# nRF24L01.net
KiCad netlist of a schematic drawn in Altium Designer
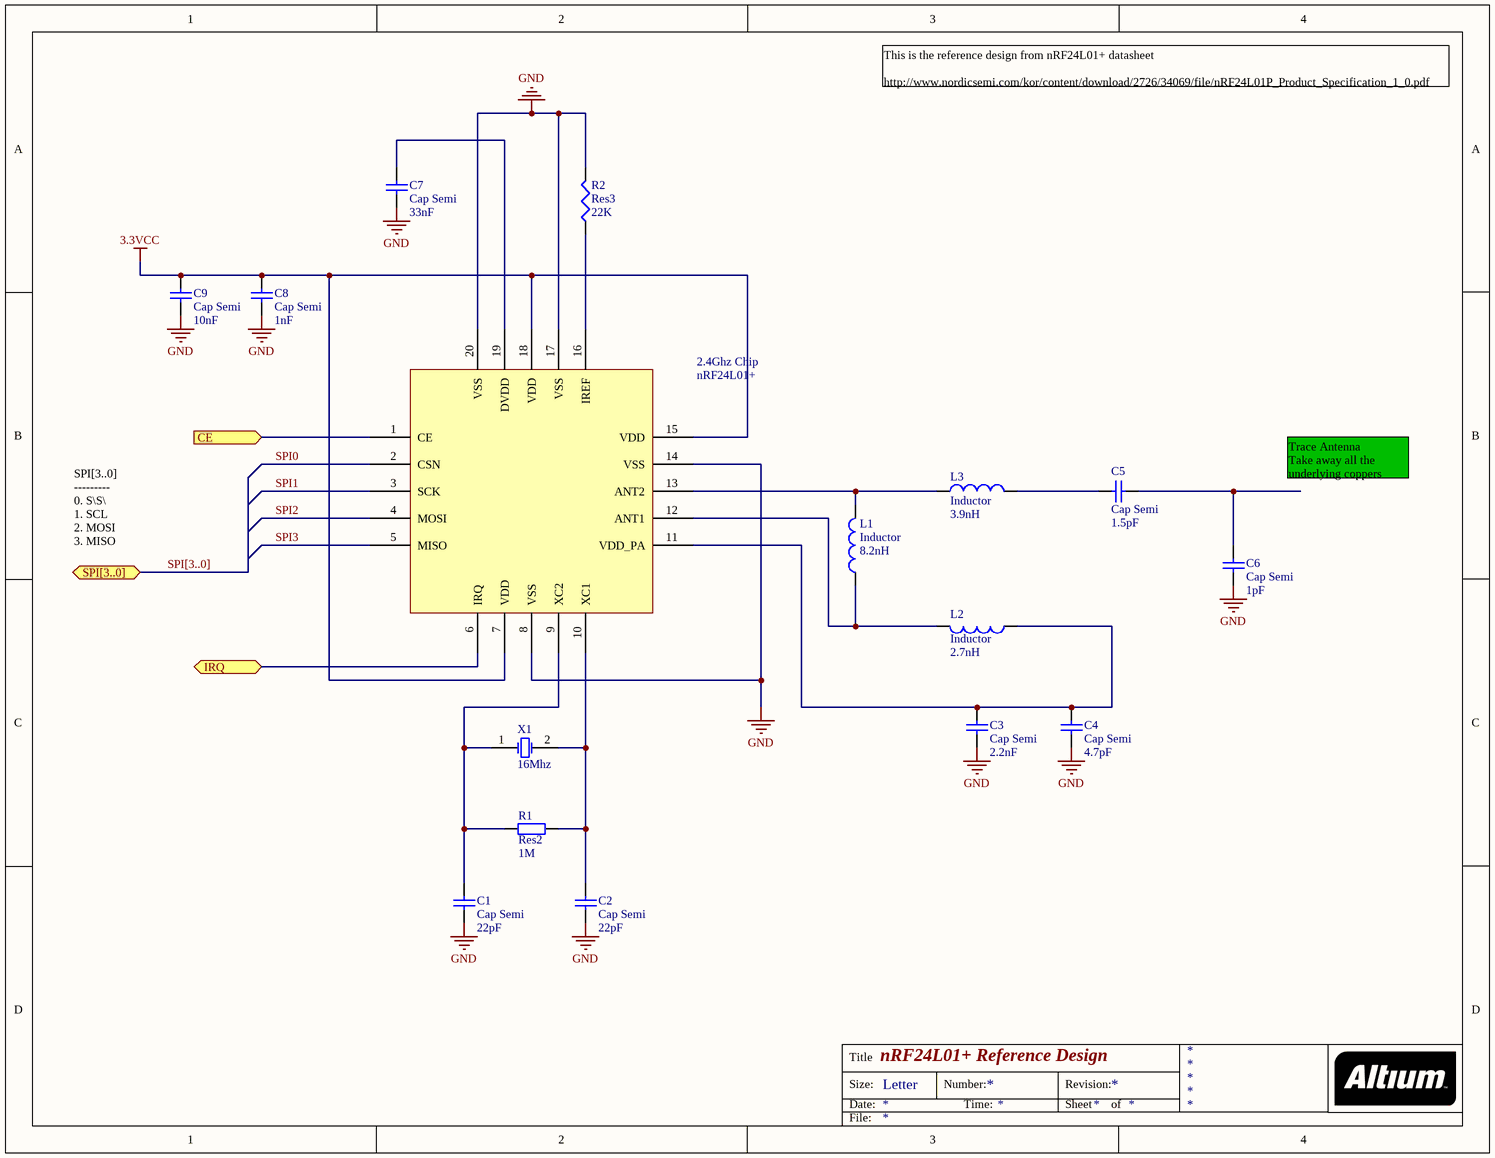
[diagram p0: nRF24L01+.SchDoc]

(export (version "E")
  (design (tool "Eeschema 10.0.6"))
  (components
    (comp (ref "2.4Ghz Chip")
      (value "nRF24L01+")
      (footprint "nRF24L01+")
      (libsource (lib "nRF24L01+") (part "nRF24L01+"))
    )
    (comp (ref "C1")
      (value "Cap Semi")
      (footprint "CAPC2012N")
      (description "Capacitor (Semiconductor SIM Model)")
      (fields (field (name "ALTIUM_VALUE") "22pF") (field (name "PUBLISHER") "Altium Limited"))
      (libsource (lib "Miscellaneous Devices") (part "Cap Semi"))
    )
    (comp (ref "C2")
      (value "Cap Semi")
      (footprint "CAPC2012N")
      (description "Capacitor (Semiconductor SIM Model)")
      (fields (field (name "ALTIUM_VALUE") "22pF") (field (name "PUBLISHER") "Altium Limited"))
      (libsource (lib "Miscellaneous Devices") (part "Cap Semi"))
    )
    (comp (ref "C3")
      (value "Cap Semi")
      (footprint "CAPC2012N")
      (description "Capacitor (Semiconductor SIM Model)")
      (fields (field (name "ALTIUM_VALUE") "2.2nF") (field (name "PUBLISHER") "Altium Limited"))
      (libsource (lib "Miscellaneous Devices") (part "Cap Semi"))
    )
    (comp (ref "C4")
      (value "Cap Semi")
      (footprint "CAPC2012N")
      (description "Capacitor (Semiconductor SIM Model)")
      (fields (field (name "ALTIUM_VALUE") "4.7pF") (field (name "PUBLISHER") "Altium Limited"))
      (libsource (lib "Miscellaneous Devices") (part "Cap Semi"))
    )
    (comp (ref "C5")
      (value "Cap Semi")
      (footprint "CAPC2012N")
      (description "Capacitor (Semiconductor SIM Model)")
      (fields (field (name "ALTIUM_VALUE") "1.5pF") (field (name "PUBLISHER") "Altium Limited"))
      (libsource (lib "Miscellaneous Devices") (part "Cap Semi"))
    )
    (comp (ref "C6")
      (value "Cap Semi")
      (footprint "CAPC2012N")
      (description "Capacitor (Semiconductor SIM Model)")
      (fields (field (name "ALTIUM_VALUE") "1pF") (field (name "PUBLISHER") "Altium Limited"))
      (libsource (lib "Miscellaneous Devices") (part "Cap Semi"))
    )
    (comp (ref "C7")
      (value "Cap Semi")
      (footprint "CAPC2012N")
      (description "Capacitor (Semiconductor SIM Model)")
      (fields (field (name "ALTIUM_VALUE") "33nF") (field (name "PUBLISHER") "Altium Limited"))
      (libsource (lib "Miscellaneous Devices") (part "Cap Semi"))
    )
    (comp (ref "C8")
      (value "Cap Semi")
      (footprint "CAPC2012N")
      (description "Capacitor (Semiconductor SIM Model)")
      (fields (field (name "ALTIUM_VALUE") "1nF") (field (name "PUBLISHER") "Altium Limited"))
      (libsource (lib "Miscellaneous Devices") (part "Cap Semi"))
    )
    (comp (ref "C9")
      (value "Cap Semi")
      (footprint "CAPC2012N")
      (description "Capacitor (Semiconductor SIM Model)")
      (fields (field (name "ALTIUM_VALUE") "10nF") (field (name "PUBLISHER") "Altium Limited"))
      (libsource (lib "Miscellaneous Devices") (part "Cap Semi"))
    )
    (comp (ref "L1")
      (value "Inductor")
      (footprint "INDC1608N")
      (fields (field (name "ALTIUM_VALUE") "8.2nH") (field (name "PUBLISHER") "Altium Limited"))
      (libsource (lib "Miscellaneous Devices") (part "Inductor"))
    )
    (comp (ref "L2")
      (value "Inductor")
      (footprint "INDC1608N")
      (fields (field (name "ALTIUM_VALUE") "2.7nH") (field (name "PUBLISHER") "Altium Limited"))
      (libsource (lib "Miscellaneous Devices") (part "Inductor"))
    )
    (comp (ref "L3")
      (value "Inductor")
      (footprint "INDC1608N")
      (fields (field (name "ALTIUM_VALUE") "3.9nH") (field (name "PUBLISHER") "Altium Limited"))
      (libsource (lib "Miscellaneous Devices") (part "Inductor"))
    )
    (comp (ref "R1")
      (value "Res2")
      (footprint "RESC2012N")
      (description "Resistor")
      (fields (field (name "ALTIUM_VALUE") "1M") (field (name "PUBLISHER") "Altium Limited"))
      (libsource (lib "Miscellaneous Devices") (part "Res2"))
    )
    (comp (ref "R2")
      (value "Res3")
      (footprint "RESC2012N")
      (description "Resistor")
      (fields (field (name "ALTIUM_VALUE") "22K") (field (name "PUBLISHER") "Altium Limited"))
      (libsource (lib "Miscellaneous Devices") (part "Res3"))
    )
    (comp (ref "X1")
      (value "16Mhz")
      (footprint "HC-49U - Through Hole")
      (description "Crystal Oscillator")
      (fields (field (name "PUBLISHER") "Altium Limited"))
      (libsource (lib "Miscellaneous Devices") (part "XTAL"))
    )
  )
  (nets
    (net (code "1") (name "/CE") (class "Default")
      (node (ref "2.4Ghz Chip") (pin "1") (pinfunction "CE_1") (pintype "passive"))
    )
    (net (code "2") (name "/IRQ") (class "Default")
      (node (ref "2.4Ghz Chip") (pin "6") (pinfunction "IRQ_6") (pintype "passive"))
    )
    (net (code "3") (name "/SPI0") (class "Default")
      (node (ref "2.4Ghz Chip") (pin "2") (pinfunction "CSN_2") (pintype "passive"))
    )
    (net (code "4") (name "/SPI1") (class "Default")
      (node (ref "2.4Ghz Chip") (pin "3") (pinfunction "SCK_3") (pintype "passive"))
    )
    (net (code "5") (name "/SPI2") (class "Default")
      (node (ref "2.4Ghz Chip") (pin "4") (pinfunction "MOSI_4") (pintype "passive"))
    )
    (net (code "6") (name "/SPI3") (class "Default")
      (node (ref "2.4Ghz Chip") (pin "5") (pinfunction "MISO_5") (pintype "passive"))
    )
    (net (code "8") (name "3.3VCC") (class "Default")
      (node (ref "2.4Ghz Chip") (pin "15") (pinfunction "VDD_15") (pintype "passive"))
      (node (ref "2.4Ghz Chip") (pin "18") (pinfunction "VDD_18") (pintype "passive"))
      (node (ref "2.4Ghz Chip") (pin "7") (pinfunction "VDD_7") (pintype "passive"))
      (node (ref "C8") (pin "2") (pinfunction "2_2") (pintype "passive"))
      (node (ref "C9") (pin "2") (pinfunction "2_2") (pintype "passive"))
    )
    (net (code "9") (name "GND") (class "Default")
      (node (ref "2.4Ghz Chip") (pin "14") (pinfunction "VSS_14") (pintype "passive"))
      (node (ref "2.4Ghz Chip") (pin "17") (pinfunction "VSS_17") (pintype "passive"))
      (node (ref "2.4Ghz Chip") (pin "20") (pinfunction "VSS_20") (pintype "passive"))
      (node (ref "2.4Ghz Chip") (pin "8") (pinfunction "VSS_8") (pintype "passive"))
      (node (ref "C1") (pin "1") (pinfunction "1_1") (pintype "passive"))
      (node (ref "C2") (pin "1") (pinfunction "1_1") (pintype "passive"))
      (node (ref "C3") (pin "1") (pinfunction "1_1") (pintype "passive"))
      (node (ref "C4") (pin "1") (pinfunction "1_1") (pintype "passive"))
      (node (ref "C6") (pin "1") (pinfunction "1_1") (pintype "passive"))
      (node (ref "C7") (pin "1") (pinfunction "1_1") (pintype "passive"))
      (node (ref "C8") (pin "1") (pinfunction "1_1") (pintype "passive"))
      (node (ref "C9") (pin "1") (pinfunction "1_1") (pintype "passive"))
      (node (ref "R2") (pin "2") (pinfunction "2_2") (pintype "passive"))
    )
    (net (code "10") (name "Net-(2.4Ghz Chip-ANT1)") (class "Default")
      (node (ref "2.4Ghz Chip") (pin "12") (pinfunction "ANT1_12") (pintype "passive"))
      (node (ref "L1") (pin "1") (pinfunction "1_1") (pintype "passive"))
      (node (ref "L2") (pin "2") (pinfunction "2_2") (pintype "passive"))
    )
    (net (code "11") (name "Net-(2.4Ghz Chip-ANT2)") (class "Default")
      (node (ref "2.4Ghz Chip") (pin "13") (pinfunction "ANT2_13") (pintype "passive"))
      (node (ref "L1") (pin "2") (pinfunction "2_2") (pintype "passive"))
      (node (ref "L3") (pin "1") (pinfunction "1_1") (pintype "passive"))
    )
    (net (code "12") (name "Net-(2.4Ghz Chip-DVDD)") (class "Default")
      (node (ref "2.4Ghz Chip") (pin "19") (pinfunction "DVDD_19") (pintype "passive"))
      (node (ref "C7") (pin "2") (pinfunction "2_2") (pintype "passive"))
    )
    (net (code "13") (name "Net-(2.4Ghz Chip-IREF)") (class "Default")
      (node (ref "2.4Ghz Chip") (pin "16") (pinfunction "IREF_16") (pintype "passive"))
      (node (ref "R2") (pin "1") (pinfunction "1_1") (pintype "passive"))
    )
    (net (code "14") (name "Net-(2.4Ghz Chip-VDD_PA)") (class "Default")
      (node (ref "2.4Ghz Chip") (pin "11") (pinfunction "VDD_PA_11") (pintype "passive"))
      (node (ref "C3") (pin "2") (pinfunction "2_2") (pintype "passive"))
      (node (ref "C4") (pin "2") (pinfunction "2_2") (pintype "passive"))
      (node (ref "L2") (pin "1") (pinfunction "1_1") (pintype "passive"))
    )
    (net (code "15") (name "Net-(2.4Ghz Chip-XC1)") (class "Default")
      (node (ref "2.4Ghz Chip") (pin "10") (pinfunction "XC1_10") (pintype "passive"))
      (node (ref "C2") (pin "2") (pinfunction "2_2") (pintype "passive"))
      (node (ref "R1") (pin "2") (pinfunction "2_2") (pintype "passive"))
      (node (ref "X1") (pin "2") (pinfunction "OSC2_2") (pintype "passive"))
    )
    (net (code "16") (name "Net-(2.4Ghz Chip-XC2)") (class "Default")
      (node (ref "2.4Ghz Chip") (pin "9") (pinfunction "XC2_9") (pintype "passive"))
      (node (ref "C1") (pin "2") (pinfunction "2_2") (pintype "passive"))
      (node (ref "R1") (pin "1") (pinfunction "1_1") (pintype "passive"))
      (node (ref "X1") (pin "1") (pinfunction "OSC1_1") (pintype "passive"))
    )
    (net (code "17") (name "Net-(C5-Pad1)") (class "Default")
      (node (ref "C5") (pin "1") (pinfunction "1_1") (pintype "passive"))
      (node (ref "C6") (pin "2") (pinfunction "2_2") (pintype "passive"))
    )
    (net (code "18") (name "Net-(C5-Pad2)") (class "Default")
      (node (ref "C5") (pin "2") (pinfunction "2_2") (pintype "passive"))
      (node (ref "L3") (pin "2") (pinfunction "2_2") (pintype "passive"))
    )
  )
)
